# Sheet1.net
KiCad netlist of a schematic drawn in Altium Designer
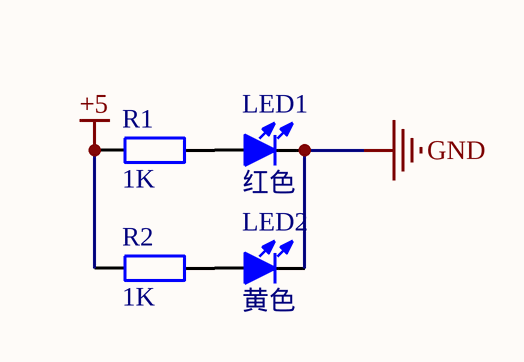
[diagram p0: Sheet1.SchDoc]

(export (version "E")
  (design (tool "Eeschema 10.0.6"))
  (components
    (comp (ref "LED1")
      (value "红色")
      (footprint "LED 0805G")
      (description "贴片LED")
      (fields (field (name "版权归属") "源创客"))
      (libsource (lib "Library1") (part "LED-SMD"))
    )
    (comp (ref "LED2")
      (value "黄色")
      (footprint "LED 0805G")
      (description "贴片LED")
      (fields (field (name "版权归属") "源创客"))
      (libsource (lib "Library1") (part "LED-SMD"))
    )
    (comp (ref "R1")
      (value "1K")
      (footprint "R 0805_L")
      (description "贴片电阻")
      (fields (field (name "版权归属") "源创客"))
      (libsource (lib "Library1") (part "R"))
    )
    (comp (ref "R2")
      (value "1K")
      (footprint "R 0805_L")
      (description "贴片电阻")
      (fields (field (name "版权归属") "源创客"))
      (libsource (lib "Library1") (part "R"))
    )
  )
  (nets
    (net (code "1") (name "+5") (class "Default")
      (node (ref "R1") (pin "2") (pinfunction "2_2") (pintype "passive"))
      (node (ref "R2") (pin "2") (pinfunction "2_2") (pintype "passive"))
    )
    (net (code "2") (name "GND") (class "Default")
      (node (ref "LED1") (pin "2") (pinfunction "K_2") (pintype "passive"))
      (node (ref "LED2") (pin "2") (pinfunction "K_2") (pintype "passive"))
    )
    (net (code "3") (name "Net-(LED1-A)") (class "Default")
      (node (ref "LED1") (pin "1") (pinfunction "A_1") (pintype "passive"))
      (node (ref "R1") (pin "1") (pinfunction "1_1") (pintype "passive"))
    )
    (net (code "4") (name "Net-(LED2-A)") (class "Default")
      (node (ref "LED2") (pin "1") (pinfunction "A_1") (pintype "passive"))
      (node (ref "R2") (pin "1") (pinfunction "1_1") (pintype "passive"))
    )
  )
)
